# Voltage_Regulator.net
KiCad netlist of a schematic drawn in Altium Designer
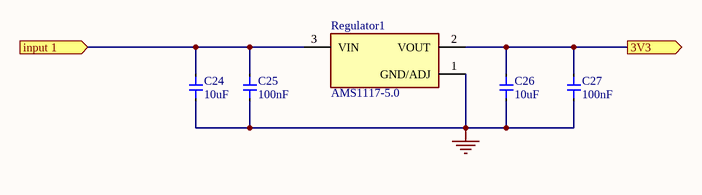
[diagram p0: Voltage_Regulator.SchDoc]

(export (version "E")
  (design (tool "Eeschema 10.0.6"))
  (components
    (comp (ref "C24")
      (value "10uF")
      (footprint "Cap 0805")
      (description "Capacitor SMD 0805")
      (libsource (lib "Altium_Lib_by_KhueNguyenCreator") (part "Cap 0805"))
    )
    (comp (ref "C25")
      (value "100nF")
      (footprint "Cap 0805")
      (description "Capacitor SMD 0805")
      (libsource (lib "Altium_Lib_by_KhueNguyenCreator") (part "Cap 0805"))
    )
    (comp (ref "C26")
      (value "10uF")
      (footprint "Cap 0805")
      (description "Capacitor SMD 0805")
      (libsource (lib "Altium_Lib_by_KhueNguyenCreator") (part "Cap 0805"))
    )
    (comp (ref "C27")
      (value "100nF")
      (footprint "Cap 0805")
      (description "Capacitor SMD 0805")
      (libsource (lib "Altium_Lib_by_KhueNguyenCreator") (part "Cap 0805"))
    )
    (comp (ref "Regulator1")
      (value "AMS1117-5.0")
      (footprint "SOT229P700X180-4N")
      (description "1A LOW DROPOUT VOLTAGE REGULATOR")
      (fields (field (name "MF") "ams"))
      (libsource (lib "AMS1117-5.0") (part "AMS1117-5.0"))
    )
  )
  (nets
    (net (code "1") (name "/3V3") (class "Default")
      (node (ref "C26") (pin "1") (pinfunction "1_1") (pintype "passive"))
      (node (ref "C27") (pin "1") (pinfunction "1_1") (pintype "passive"))
      (node (ref "Regulator1") (pin "2") (pinfunction "VOUT_2") (pintype "passive"))
    )
    (net (code "2") (name "/input 1") (class "Default")
      (node (ref "C24") (pin "1") (pinfunction "1_1") (pintype "passive"))
      (node (ref "C25") (pin "1") (pinfunction "1_1") (pintype "passive"))
      (node (ref "Regulator1") (pin "3") (pinfunction "VIN_3") (pintype "passive"))
    )
    (net (code "3") (name "GND") (class "Default")
      (node (ref "C24") (pin "2") (pinfunction "2_2") (pintype "passive"))
      (node (ref "C25") (pin "2") (pinfunction "2_2") (pintype "passive"))
      (node (ref "C26") (pin "2") (pinfunction "2_2") (pintype "passive"))
      (node (ref "C27") (pin "2") (pinfunction "2_2") (pintype "passive"))
      (node (ref "Regulator1") (pin "1") (pinfunction "GND/ADJ_1") (pintype "passive"))
    )
  )
)
